# CHR_ver1.net
KiCad netlist of a schematic drawn in EAGLE
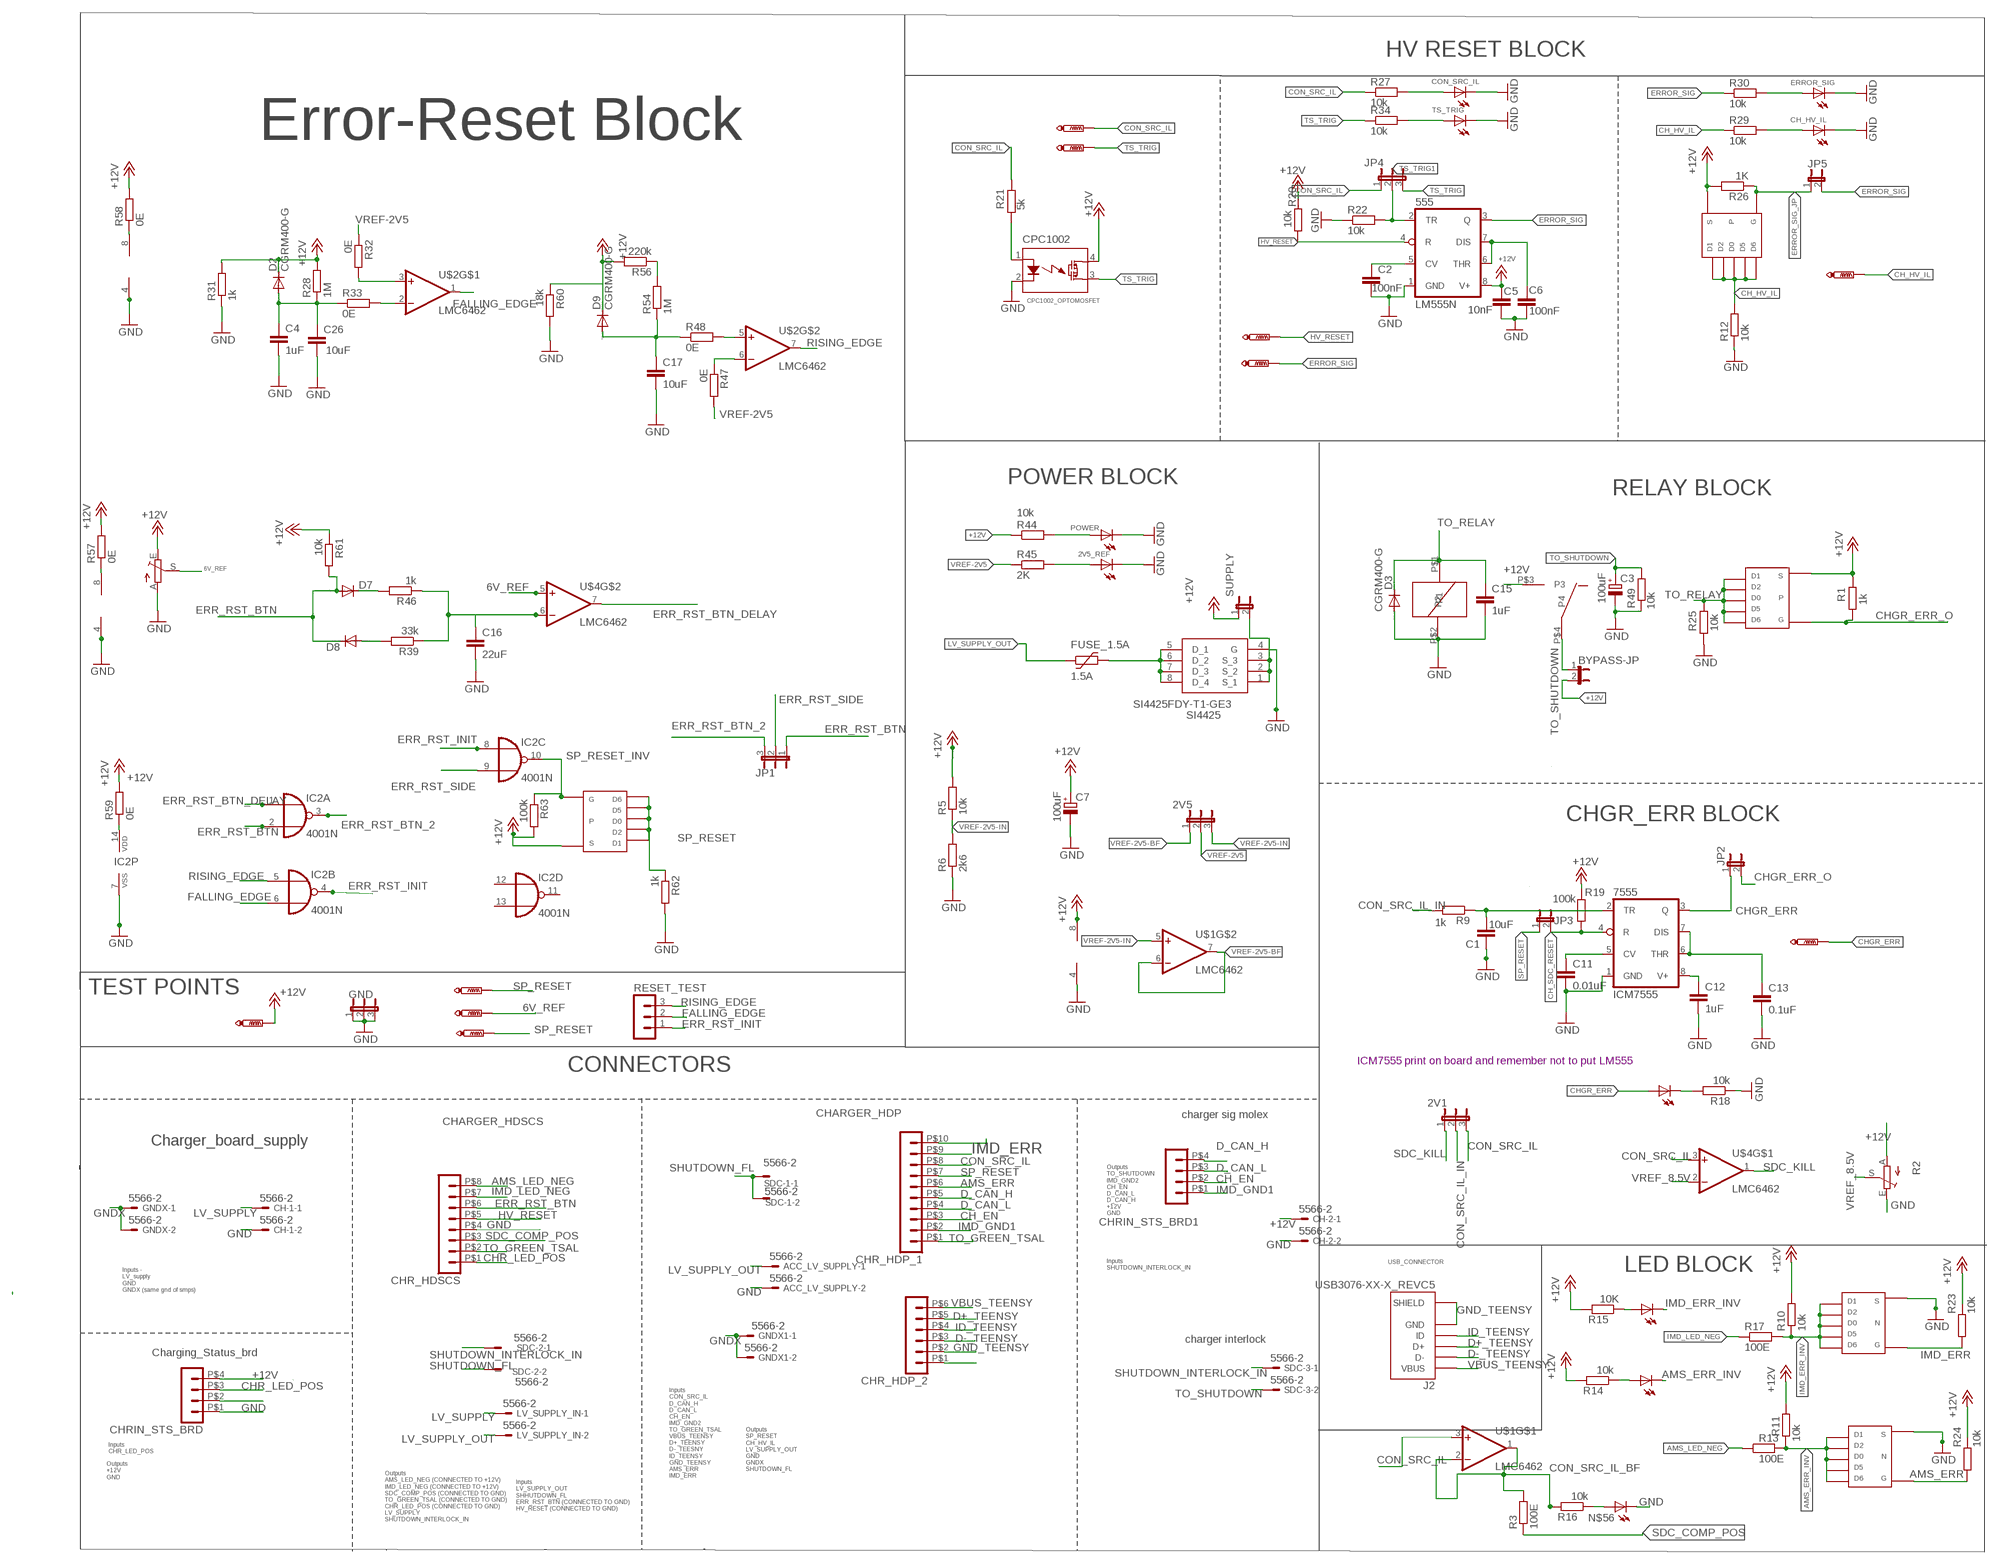
[diagram p0: schematic, sheet 1]

(export (version "E")
  (design (tool "Eeschema 10.0.6"))
  (components
    (comp (ref "+12V")
      (value "PTR1PAD1-13")
      (footprint "eagle-import:P1-13")
      (libsource (lib "eagle-import") (part "PTR1PAD1-13"))
    )
    (comp (ref "2V1")
      (value "JP2E")
      (footprint "eagle-import:JP2")
      (libsource (lib "eagle-import") (part "JP2E"))
    )
    (comp (ref "2V5")
      (value "JP2E")
      (footprint "eagle-import:JP2")
      (libsource (lib "eagle-import") (part "JP2E"))
    )
    (comp (ref "2V5_REF")
      (value "LED-FKIT-1206")
      (footprint "eagle-import:FKIT-LED-1206")
      (libsource (lib "eagle-import") (part "LED-FKIT-1206"))
    )
    (comp (ref "555")
      (value "LM555N")
      (footprint "eagle-import:DIL08")
      (libsource (lib "eagle-import") (part "555NLM"))
    )
    (comp (ref "7555")
      (value "ICM7555")
      (footprint "eagle-import:DIL08")
      (libsource (lib "eagle-import") (part "555NLM"))
    )
    (comp (ref "ACC_LV_SUPPLY")
      (value "5566-2")
      (footprint "eagle-import:5566-2")
      (fields (field (name "MF") "MOLEX"))
      (libsource (lib "eagle-import") (part "5566-2"))
    )
    (comp (ref "AMS")
      (value "LED-FKIT-1206")
      (footprint "eagle-import:FKIT-LED-1206")
      (libsource (lib "eagle-import") (part "LED-FKIT-1206"))
    )
    (comp (ref "AMS1")
      (value "LED-FKIT-1206")
      (footprint "eagle-import:FKIT-LED-1206")
      (libsource (lib "eagle-import") (part "LED-FKIT-1206"))
    )
    (comp (ref "BYPASS-JP")
      (value "JP1E")
      (footprint "eagle-import:JP1")
      (libsource (lib "eagle-import") (part "JP1E"))
    )
    (comp (ref "C1")
      (value "10uF")
      (footprint "eagle-import:C0805")
      (libsource (lib "eagle-import") (part "C-EUC0805"))
    )
    (comp (ref "C2")
      (value "100nF")
      (footprint "eagle-import:C0805")
      (libsource (lib "eagle-import") (part "C-EUC0805"))
    )
    (comp (ref "C3")
      (value "100uF")
      (footprint "eagle-import:E2,5-6")
      (libsource (lib "eagle-import") (part "CPOL-EUE2.5-6"))
    )
    (comp (ref "C4")
      (value "1uF")
      (footprint "eagle-import:C0805")
      (libsource (lib "eagle-import") (part "C-EUC0805"))
    )
    (comp (ref "C5")
      (value "10nF")
      (footprint "eagle-import:C0805")
      (libsource (lib "eagle-import") (part "C-EUC0805"))
    )
    (comp (ref "C6")
      (value "100nF")
      (footprint "eagle-import:C0805")
      (libsource (lib "eagle-import") (part "C-EUC0805"))
    )
    (comp (ref "C7")
      (value "100uF")
      (footprint "eagle-import:E2,5-6")
      (libsource (lib "eagle-import") (part "CPOL-EUE2.5-6"))
    )
    (comp (ref "C11")
      (value "0.01uF")
      (footprint "eagle-import:C0805")
      (libsource (lib "eagle-import") (part "C-EUC0805"))
    )
    (comp (ref "C12")
      (value "1uF")
      (footprint "eagle-import:C0805")
      (libsource (lib "eagle-import") (part "C-EUC0805"))
    )
    (comp (ref "C13")
      (value "0.1uF")
      (footprint "eagle-import:C0805")
      (libsource (lib "eagle-import") (part "C-EUC0805"))
    )
    (comp (ref "C15")
      (value "1uF")
      (footprint "eagle-import:C0805")
      (libsource (lib "eagle-import") (part "C-EUC0805"))
    )
    (comp (ref "C16")
      (value "22uF")
      (footprint "eagle-import:C0805")
      (libsource (lib "eagle-import") (part "C-EUC0805"))
    )
    (comp (ref "C17")
      (value "10uF")
      (footprint "eagle-import:C0805")
      (libsource (lib "eagle-import") (part "C-EUC0805"))
    )
    (comp (ref "C26")
      (value "10uF")
      (footprint "eagle-import:C0805")
      (libsource (lib "eagle-import") (part "C-EUC0805"))
    )
    (comp (ref "CH-1")
      (value "5566-2")
      (footprint "eagle-import:5566-2")
      (fields (field (name "MF") "MOLEX"))
      (libsource (lib "eagle-import") (part "5566-2"))
    )
    (comp (ref "CH-2")
      (value "5566-2")
      (footprint "eagle-import:5566-2")
      (fields (field (name "MF") "MOLEX"))
      (libsource (lib "eagle-import") (part "5566-2"))
    )
    (comp (ref "CH-HV-IL")
      (value "PTR1PAD1-13")
      (footprint "eagle-import:P1-13")
      (libsource (lib "eagle-import") (part "PTR1PAD1-13"))
    )
    (comp (ref "CHGR-ERR")
      (value "PTR1PAD1-13")
      (footprint "eagle-import:P1-13")
      (libsource (lib "eagle-import") (part "PTR1PAD1-13"))
    )
    (comp (ref "CHGR_ERR")
      (value "LED-FKIT-1206")
      (footprint "eagle-import:FKIT-LED-1206")
      (libsource (lib "eagle-import") (part "LED-FKIT-1206"))
    )
    (comp (ref "CHRIN_STS_BRD")
      (value "HEADER_POS4_44914-0401")
      (footprint "eagle-import:44914-0401")
      (libsource (lib "eagle-import") (part "HEADER_POS4_?44914-0401"))
    )
    (comp (ref "CHRIN_STS_BRD1")
      (value "HEADER_POS4_44914-0401")
      (footprint "eagle-import:44914-0401")
      (libsource (lib "eagle-import") (part "HEADER_POS4_?44914-0401"))
    )
    (comp (ref "CHR_HDP_1")
      (value "HEADER_POS10_44914-1001")
      (footprint "eagle-import:44914-1001")
      (libsource (lib "eagle-import") (part "HEADER_POS10_?44914-1001"))
    )
    (comp (ref "CHR_HDP_2")
      (value "HEADER_POS6_44914-0601")
      (footprint "eagle-import:44914-0601")
      (libsource (lib "eagle-import") (part "HEADER_POS6_?44914-0601"))
    )
    (comp (ref "CHR_HDSCS")
      (value "HEADER_POS8_44914-0801")
      (footprint "eagle-import:44914-0801")
      (libsource (lib "eagle-import") (part "HEADER_POS8_?44914-0801"))
    )
    (comp (ref "CH_HV_IL")
      (value "LED-FKIT-1206")
      (footprint "eagle-import:FKIT-LED-1206")
      (libsource (lib "eagle-import") (part "LED-FKIT-1206"))
    )
    (comp (ref "CON-SRC-IL")
      (value "PTR1PAD1-13")
      (footprint "eagle-import:P1-13")
      (libsource (lib "eagle-import") (part "PTR1PAD1-13"))
    )
    (comp (ref "CON_SRC_IL")
      (value "LED-FKIT-1206")
      (footprint "eagle-import:FKIT-LED-1206")
      (libsource (lib "eagle-import") (part "LED-FKIT-1206"))
    )
    (comp (ref "CPC1002")
      (value "CPC1002_OPTOMOSFET")
      (footprint "eagle-import:SOP04")
      (libsource (lib "eagle-import") (part "CPC1002_OPTOMOSFET"))
    )
    (comp (ref "D2")
      (value "CGRM400-G")
      (footprint "eagle-import:SOD-123_MINI-SMA")
      (libsource (lib "eagle-import") (part "CGRM400-G"))
    )
    (comp (ref "D3")
      (value "CGRM400-G")
      (footprint "eagle-import:SOD-123_MINI-SMA")
      (libsource (lib "eagle-import") (part "CGRM400-G"))
    )
    (comp (ref "D7")
      (value "DIODE-DO214AC")
      (footprint "eagle-import:DO214AC")
      (libsource (lib "eagle-import") (part "DIODE-DO214AC"))
    )
    (comp (ref "D8")
      (value "DIODE-DO214AC")
      (footprint "eagle-import:DO214AC")
      (libsource (lib "eagle-import") (part "DIODE-DO214AC"))
    )
    (comp (ref "D9")
      (value "CGRM400-G")
      (footprint "eagle-import:SOD-123_MINI-SMA")
      (libsource (lib "eagle-import") (part "CGRM400-G"))
    )
    (comp (ref "ERROR-SIG")
      (value "PTR1PAD1-13")
      (footprint "eagle-import:P1-13")
      (libsource (lib "eagle-import") (part "PTR1PAD1-13"))
    )
    (comp (ref "ERROR_SIG")
      (value "LED-FKIT-1206")
      (footprint "eagle-import:FKIT-LED-1206")
      (libsource (lib "eagle-import") (part "LED-FKIT-1206"))
    )
    (comp (ref "FUSE_1.5A")
      (value "1.5A")
      (footprint "eagle-import:1206L")
      (fields (field (name "MFR") "Littelfuse"))
      (libsource (lib "eagle-import") (part "1206L"))
    )
    (comp (ref "GND")
      (value "JP2E")
      (footprint "eagle-import:JP2")
      (libsource (lib "eagle-import") (part "JP2E"))
    )
    (comp (ref "GNDX")
      (value "5566-2")
      (footprint "eagle-import:5566-2")
      (fields (field (name "MF") "MOLEX"))
      (libsource (lib "eagle-import") (part "5566-2"))
    )
    (comp (ref "GNDX1")
      (value "5566-2")
      (footprint "eagle-import:5566-2")
      (fields (field (name "MF") "MOLEX"))
      (libsource (lib "eagle-import") (part "5566-2"))
    )
    (comp (ref "HV-RESET")
      (value "PTR1PAD1-13")
      (footprint "eagle-import:P1-13")
      (libsource (lib "eagle-import") (part "PTR1PAD1-13"))
    )
    (comp (ref "IC2")
      (value "4001N")
      (footprint "eagle-import:DIL14")
      (libsource (lib "eagle-import") (part "4001N"))
    )
    (comp (ref "IMD")
      (value "LED-FKIT-1206")
      (footprint "eagle-import:FKIT-LED-1206")
      (libsource (lib "eagle-import") (part "LED-FKIT-1206"))
    )
    (comp (ref "J2")
      (value "USB3076-XX-X_REVC5")
      (footprint "eagle-import:GCT_USB3076-XX-X_REVC5")
      (fields (field (name "MF") "Global Connector Technology") (field (name "MP") "USB3076-30-A"))
      (libsource (lib "eagle-import") (part "USB3076-XX-X_REVC5"))
    )
    (comp (ref "JP1")
      (value "JP2E")
      (footprint "eagle-import:JP2")
      (libsource (lib "eagle-import") (part "JP2E"))
    )
    (comp (ref "JP2")
      (value "JP1E")
      (footprint "eagle-import:JP1")
      (libsource (lib "eagle-import") (part "JP1E"))
    )
    (comp (ref "JP3")
      (value "JP1E")
      (footprint "eagle-import:JP1")
      (libsource (lib "eagle-import") (part "JP1E"))
    )
    (comp (ref "JP4")
      (value "JP2E")
      (footprint "eagle-import:JP2")
      (libsource (lib "eagle-import") (part "JP2E"))
    )
    (comp (ref "JP5")
      (value "JP1E")
      (footprint "eagle-import:JP1")
      (libsource (lib "eagle-import") (part "JP1E"))
    )
    (comp (ref "LV_SUPPLY_IN")
      (value "5566-2")
      (footprint "eagle-import:5566-2")
      (fields (field (name "MF") "MOLEX"))
      (libsource (lib "eagle-import") (part "5566-2"))
    )
    (comp (ref "POWER")
      (value "LED-FKIT-1206")
      (footprint "eagle-import:FKIT-LED-1206")
      (libsource (lib "eagle-import") (part "LED-FKIT-1206"))
    )
    (comp (ref "R1")
      (value "1k")
      (footprint "eagle-import:R0805")
      (libsource (lib "eagle-import") (part "R-EU_R0805"))
    )
    (comp (ref "R2")
      (value "TRIM_EU-S63S")
      (footprint "eagle-import:S63S")
      (libsource (lib "eagle-import") (part "TRIM_EU-S63S"))
    )
    (comp (ref "R3")
      (value "100E")
      (footprint "eagle-import:M0805")
      (libsource (lib "eagle-import") (part "rcl_334_R-EU_M0805"))
    )
    (comp (ref "R5")
      (value "10k")
      (footprint "eagle-import:R0805")
      (libsource (lib "eagle-import") (part "R-EU_R0805"))
    )
    (comp (ref "R6")
      (value "2k6")
      (footprint "eagle-import:R0805")
      (libsource (lib "eagle-import") (part "R-EU_R0805"))
    )
    (comp (ref "R9")
      (value "1k")
      (footprint "eagle-import:R0805")
      (libsource (lib "eagle-import") (part "R-EU_R0805"))
    )
    (comp (ref "R10")
      (value "10k")
      (footprint "eagle-import:R0805")
      (libsource (lib "eagle-import") (part "R-EU_R0805"))
    )
    (comp (ref "R11")
      (value "10k")
      (footprint "eagle-import:R0805")
      (libsource (lib "eagle-import") (part "R-EU_R0805"))
    )
    (comp (ref "R12")
      (value "10k")
      (footprint "eagle-import:R0805")
      (libsource (lib "eagle-import") (part "R-EU_R0805"))
    )
    (comp (ref "R13")
      (value "100E")
      (footprint "eagle-import:M0805")
      (libsource (lib "eagle-import") (part "rcl_334_R-EU_M0805"))
    )
    (comp (ref "R14")
      (value "10k")
      (footprint "eagle-import:M0805")
      (libsource (lib "eagle-import") (part "rcl_334_R-EU_M0805"))
    )
    (comp (ref "R15")
      (value "10K")
      (footprint "eagle-import:M0805")
      (libsource (lib "eagle-import") (part "rcl_334_R-EU_M0805"))
    )
    (comp (ref "R16")
      (value "10k")
      (footprint "eagle-import:M0805")
      (libsource (lib "eagle-import") (part "rcl_334_R-EU_M0805"))
    )
    (comp (ref "R17")
      (value "100E")
      (footprint "eagle-import:M0805")
      (libsource (lib "eagle-import") (part "rcl_334_R-EU_M0805"))
    )
    (comp (ref "R18")
      (value "10k")
      (footprint "eagle-import:R0805")
      (libsource (lib "eagle-import") (part "R-EU_R0805"))
    )
    (comp (ref "R19")
      (value "100k")
      (footprint "eagle-import:R0805")
      (libsource (lib "eagle-import") (part "R-EU_R0805"))
    )
    (comp (ref "R20")
      (value "10k")
      (footprint "eagle-import:R0805")
      (libsource (lib "eagle-import") (part "R-EU_R0805"))
    )
    (comp (ref "R21")
      (value "5k")
      (footprint "eagle-import:R0805")
      (libsource (lib "eagle-import") (part "R-EU_R0805"))
    )
    (comp (ref "R22")
      (value "10k")
      (footprint "eagle-import:R0805")
      (libsource (lib "eagle-import") (part "R-EU_R0805"))
    )
    (comp (ref "R23")
      (value "10k")
      (footprint "eagle-import:R0805")
      (libsource (lib "eagle-import") (part "R-EU_R0805"))
    )
    (comp (ref "R24")
      (value "10k")
      (footprint "eagle-import:R0805")
      (libsource (lib "eagle-import") (part "R-EU_R0805"))
    )
    (comp (ref "R25")
      (value "10k")
      (footprint "eagle-import:R0805")
      (libsource (lib "eagle-import") (part "R-EU_R0805"))
    )
    (comp (ref "R26")
      (value "1K")
      (footprint "eagle-import:R0805")
      (libsource (lib "eagle-import") (part "R-EU_R0805"))
    )
    (comp (ref "R27")
      (value "10k")
      (footprint "eagle-import:R0805")
      (libsource (lib "eagle-import") (part "R-EU_R0805"))
    )
    (comp (ref "R28")
      (value "1M")
      (footprint "eagle-import:R0805")
      (libsource (lib "eagle-import") (part "R-EU_R0805"))
    )
    (comp (ref "R29")
      (value "10k")
      (footprint "eagle-import:R0805")
      (libsource (lib "eagle-import") (part "R-EU_R0805"))
    )
    (comp (ref "R30")
      (value "10k")
      (footprint "eagle-import:R0805")
      (libsource (lib "eagle-import") (part "R-EU_R0805"))
    )
    (comp (ref "R31")
      (value "1k")
      (footprint "eagle-import:R0805")
      (libsource (lib "eagle-import") (part "R-EU_R0805"))
    )
    (comp (ref "R32")
      (value "0E")
      (footprint "eagle-import:R0805")
      (libsource (lib "eagle-import") (part "R-EU_R0805"))
    )
    (comp (ref "R33")
      (value "0E")
      (footprint "eagle-import:R0805")
      (libsource (lib "eagle-import") (part "R-EU_R0805"))
    )
    (comp (ref "R34")
      (value "10k")
      (footprint "eagle-import:R0805")
      (libsource (lib "eagle-import") (part "R-EU_R0805"))
    )
    (comp (ref "R39")
      (value "33k")
      (footprint "eagle-import:R0805")
      (libsource (lib "eagle-import") (part "R-EU_R0805"))
    )
    (comp (ref "R44")
      (value "10k")
      (footprint "eagle-import:R0805")
      (libsource (lib "eagle-import") (part "R-EU_R0805"))
    )
    (comp (ref "R45")
      (value "2K")
      (footprint "eagle-import:R0805")
      (libsource (lib "eagle-import") (part "R-EU_R0805"))
    )
    (comp (ref "R46")
      (value "1k")
      (footprint "eagle-import:R0805")
      (libsource (lib "eagle-import") (part "R-EU_R0805"))
    )
    (comp (ref "R47")
      (value "0E")
      (footprint "eagle-import:R0805")
      (libsource (lib "eagle-import") (part "R-EU_R0805"))
    )
    (comp (ref "R48")
      (value "0E")
      (footprint "eagle-import:R0805")
      (libsource (lib "eagle-import") (part "R-EU_R0805"))
    )
    (comp (ref "R49")
      (value "10k")
      (footprint "eagle-import:R0805")
      (libsource (lib "eagle-import") (part "R-EU_R0805"))
    )
    (comp (ref "R54")
      (value "1M")
      (footprint "eagle-import:R0805")
      (libsource (lib "eagle-import") (part "R-EU_R0805"))
    )
    (comp (ref "R56")
      (value "220k")
      (footprint "eagle-import:R0805")
      (libsource (lib "eagle-import") (part "R-EU_R0805"))
    )
    (comp (ref "R57")
      (value "0E")
      (footprint "eagle-import:R0805")
      (libsource (lib "eagle-import") (part "R-EU_R0805"))
    )
    (comp (ref "R58")
      (value "0E")
      (footprint "eagle-import:R0805")
      (libsource (lib "eagle-import") (part "R-EU_R0805"))
    )
    (comp (ref "R59")
      (value "0E")
      (footprint "eagle-import:R0805")
      (libsource (lib "eagle-import") (part "R-EU_R0805"))
    )
    (comp (ref "R60")
      (value "18k")
      (footprint "eagle-import:R0805")
      (libsource (lib "eagle-import") (part "R-EU_R0805"))
    )
    (comp (ref "R61")
      (value "10k")
      (footprint "eagle-import:R0805")
      (libsource (lib "eagle-import") (part "R-EU_R0805"))
    )
    (comp (ref "R62")
      (value "1k")
      (footprint "eagle-import:R0805")
      (libsource (lib "eagle-import") (part "R-EU_R0805"))
    )
    (comp (ref "R63")
      (value "100k")
      (footprint "eagle-import:R0805")
      (libsource (lib "eagle-import") (part "R-EU_R0805"))
    )
    (comp (ref "REF_POT1")
      (value "10k")
      (footprint "eagle-import:S63S")
      (libsource (lib "eagle-import") (part "TRIM_EU-S63S"))
    )
    (comp (ref "RESET_TEST")
      (value "MA03-1")
      (footprint "eagle-import:MA03-1")
      (libsource (lib "eagle-import") (part "MA03-1"))
    )
    (comp (ref "SDC-1")
      (value "5566-2")
      (footprint "eagle-import:5566-2")
      (fields (field (name "MF") "MOLEX"))
      (libsource (lib "eagle-import") (part "5566-2"))
    )
    (comp (ref "SDC-2")
      (value "5566-2")
      (footprint "eagle-import:5566-2")
      (fields (field (name "MF") "MOLEX"))
      (libsource (lib "eagle-import") (part "5566-2"))
    )
    (comp (ref "SDC-3")
      (value "5566-2")
      (footprint "eagle-import:5566-2")
      (fields (field (name "MF") "MOLEX"))
      (libsource (lib "eagle-import") (part "5566-2"))
    )
    (comp (ref "SI4425")
      (value "SI4425FDY-T1-GE3")
      (footprint "eagle-import:SOIC127P600X175-8N")
      (fields (field (name "MOUSER_PART_NUMBER") "78-SI4425FDY-T1-GE3"))
      (libsource (lib "eagle-import") (part "SI4425FDY-T1-GE3"))
    )
    (comp (ref "SP_RESET")
      (value "PTR1PAD1-13")
      (footprint "eagle-import:P1-13")
      (libsource (lib "eagle-import") (part "PTR1PAD1-13"))
    )
    (comp (ref "SP_RESET1")
      (value "PTR1PAD1-13")
      (footprint "eagle-import:P1-13")
      (libsource (lib "eagle-import") (part "PTR1PAD1-13"))
    )
    (comp (ref "SP_RESET2")
      (value "PTR1PAD1-13")
      (footprint "eagle-import:P1-13")
      (libsource (lib "eagle-import") (part "PTR1PAD1-13"))
    )
    (comp (ref "SUPPLY")
      (value "JP1E")
      (footprint "eagle-import:JP1")
      (libsource (lib "eagle-import") (part "JP1E"))
    )
    (comp (ref "TS-TRIG")
      (value "PTR1PAD1-13")
      (footprint "eagle-import:P1-13")
      (libsource (lib "eagle-import") (part "PTR1PAD1-13"))
    )
    (comp (ref "TS_TRIG")
      (value "LED-FKIT-1206")
      (footprint "eagle-import:FKIT-LED-1206")
      (libsource (lib "eagle-import") (part "LED-FKIT-1206"))
    )
    (comp (ref "U$1")
      (value "LMC6462")
      (footprint "eagle-import:S08")
      (libsource (lib "eagle-import") (part "LMC6462"))
    )
    (comp (ref "U$2")
      (value "LMC6462")
      (footprint "eagle-import:S08")
      (libsource (lib "eagle-import") (part "LMC6462"))
    )
    (comp (ref "U$3")
      (value "TSOP-6_PMOS")
      (footprint "eagle-import:TSOP-6_PMOS")
      (libsource (lib "eagle-import") (part "TSOP-6_MOS_TSOP-6_PMOS"))
    )
    (comp (ref "U$4")
      (value "LMC6462")
      (footprint "eagle-import:S08")
      (libsource (lib "eagle-import") (part "LMC6462"))
    )
    (comp (ref "U$5")
      (value "TSOP-6_NMOS")
      (footprint "eagle-import:TSOP-6_NMOS")
      (libsource (lib "eagle-import") (part "TSOP-6_NMOS"))
    )
    (comp (ref "U$7")
      (value "TSOP-6_NMOS")
      (footprint "eagle-import:TSOP-6_NMOS")
      (libsource (lib "eagle-import") (part "TSOP-6_NMOS"))
    )
    (comp (ref "U$8")
      (value "TSOP-6_PMOS")
      (footprint "eagle-import:TSOP-6_PMOS")
      (libsource (lib "eagle-import") (part "TSOP-6_PMOS"))
    )
    (comp (ref "U$9")
      (value "G6DN_RELAY")
      (footprint "eagle-import:G6DN_RELAY")
      (libsource (lib "eagle-import") (part "G6DN_RELAY"))
    )
    (comp (ref "U$11")
      (value "TSOP-6_PMOS")
      (footprint "eagle-import:TSOP-6_PMOS")
      (libsource (lib "eagle-import") (part "TSOP-6_MOS_TSOP-6_PMOS"))
    )
  )
  (nets
    (net (code "1") (name "+12V") (class "Default")
      (node (ref "+12V") (pin "TP") (pinfunction "TP_TP") (pintype "input"))
      (node (ref "555") (pin "8") (pinfunction "V+_8") (pintype "power_in"))
      (node (ref "7555") (pin "8") (pinfunction "V+_8") (pintype "power_in"))
      (node (ref "BYPASS-JP") (pin "2") (pinfunction "2_2") (pintype "passive"))
      (node (ref "C12") (pin "1") (pinfunction "1_1") (pintype "passive"))
      (node (ref "C5") (pin "1") (pinfunction "1_1") (pintype "passive"))
      (node (ref "C7") (pin "+") (pinfunction "+_+") (pintype "passive"))
      (node (ref "CH-2") (pin "1") (pinfunction "S_1") (pintype "passive"))
      (node (ref "CHRIN_STS_BRD") (pin "P$4") (pinfunction "4_P$4") (pintype "passive"))
      (node (ref "CPC1002") (pin "4") (pinfunction "4_4") (pintype "passive"))
      (node (ref "D2") (pin "C") (pinfunction "C_C") (pintype "passive"))
      (node (ref "D9") (pin "C") (pinfunction "C_C") (pintype "passive"))
      (node (ref "R1") (pin "2") (pinfunction "2_2") (pintype "passive"))
      (node (ref "R10") (pin "2") (pinfunction "2_2") (pintype "passive"))
      (node (ref "R11") (pin "2") (pinfunction "2_2") (pintype "passive"))
      (node (ref "R14") (pin "2") (pinfunction "2_2") (pintype "passive"))
      (node (ref "R15") (pin "2") (pinfunction "2_2") (pintype "passive"))
      (node (ref "R19") (pin "1") (pinfunction "1_1") (pintype "passive"))
      (node (ref "R2") (pin "A") (pinfunction "A_A") (pintype "passive"))
      (node (ref "R20") (pin "2") (pinfunction "2_2") (pintype "passive"))
      (node (ref "R23") (pin "2") (pinfunction "2_2") (pintype "passive"))
      (node (ref "R24") (pin "2") (pinfunction "2_2") (pintype "passive"))
      (node (ref "R26") (pin "2") (pinfunction "2_2") (pintype "passive"))
      (node (ref "R28") (pin "2") (pinfunction "2_2") (pintype "passive"))
      (node (ref "R31") (pin "2") (pinfunction "2_2") (pintype "passive"))
      (node (ref "R44") (pin "1") (pinfunction "1_1") (pintype "passive"))
      (node (ref "R5") (pin "2") (pinfunction "2_2") (pintype "passive"))
      (node (ref "R56") (pin "2") (pinfunction "2_2") (pintype "passive"))
      (node (ref "R57") (pin "2") (pinfunction "2_2") (pintype "passive"))
      (node (ref "R58") (pin "2") (pinfunction "2_2") (pintype "passive"))
      (node (ref "R59") (pin "2") (pinfunction "2_2") (pintype "passive"))
      (node (ref "R60") (pin "1") (pinfunction "1_1") (pintype "passive"))
      (node (ref "R61") (pin "1") (pinfunction "1_1") (pintype "passive"))
      (node (ref "R63") (pin "2") (pinfunction "2_2") (pintype "passive"))
      (node (ref "REF_POT1") (pin "E") (pinfunction "E_E") (pintype "passive"))
      (node (ref "SUPPLY") (pin "1") (pinfunction "1_1") (pintype "passive"))
      (node (ref "U$1") (pin "8") (pinfunction "V+_8") (pintype "power_in"))
      (node (ref "U$11") (pin "S") (pinfunction "S_S") (pintype "bidirectional"))
      (node (ref "U$3") (pin "S") (pinfunction "S_S") (pintype "bidirectional"))
      (node (ref "U$8") (pin "S") (pinfunction "S_S") (pintype "bidirectional"))
      (node (ref "U$9") (pin "P$3") (pinfunction "P3_P$3") (pintype "bidirectional"))
    )
    (net (code "2") (name "6V_REF") (class "Default")
      (node (ref "REF_POT1") (pin "S") (pinfunction "S_S") (pintype "passive"))
      (node (ref "SP_RESET1") (pin "TP") (pinfunction "TP_TP") (pintype "input"))
      (node (ref "U$4") (pin "5") (pinfunction "+IN_5") (pintype "input"))
    )
    (net (code "3") (name "AMS_ERR") (class "Default")
      (node (ref "CHR_HDP_1") (pin "P$6") (pinfunction "6_P$6") (pintype "passive"))
      (node (ref "R24") (pin "1") (pinfunction "1_1") (pintype "passive"))
      (node (ref "U$5") (pin "G") (pinfunction "G_G") (pintype "bidirectional"))
    )
    (net (code "4") (name "AMS_ERR_INV") (class "Default")
      (node (ref "AMS") (pin "C") (pinfunction "C_C") (pintype "passive"))
      (node (ref "R11") (pin "1") (pinfunction "1_1") (pintype "passive"))
      (node (ref "R13") (pin "2") (pinfunction "2_2") (pintype "passive"))
      (node (ref "U$5") (pin "1") (pinfunction "1_1") (pintype "bidirectional"))
      (node (ref "U$5") (pin "2") (pinfunction "2_2") (pintype "bidirectional"))
      (node (ref "U$5") (pin "5") (pinfunction "5_5") (pintype "bidirectional"))
      (node (ref "U$5") (pin "6") (pinfunction "6_6") (pintype "bidirectional"))
      (node (ref "U$5") (pin "D") (pinfunction "D0_D") (pintype "bidirectional"))
    )
    (net (code "5") (name "AMS_LED_NEG") (class "Default")
      (node (ref "CHR_HDSCS") (pin "P$8") (pinfunction "8_P$8") (pintype "passive"))
      (node (ref "R13") (pin "1") (pinfunction "1_1") (pintype "passive"))
    )
    (net (code "6") (name "CHGR_ERR") (class "Default")
      (node (ref "7555") (pin "3") (pinfunction "Q_3") (pintype "output"))
      (node (ref "CHGR-ERR") (pin "TP") (pinfunction "TP_TP") (pintype "input"))
      (node (ref "CHGR_ERR") (pin "A") (pinfunction "A_A") (pintype "passive"))
      (node (ref "JP2") (pin "1") (pinfunction "1_1") (pintype "passive"))
    )
    (net (code "7") (name "CHGR_ERR_O") (class "Default")
      (node (ref "JP2") (pin "2") (pinfunction "2_2") (pintype "passive"))
      (node (ref "R1") (pin "1") (pinfunction "1_1") (pintype "passive"))
      (node (ref "U$3") (pin "G") (pinfunction "G_G") (pintype "bidirectional"))
    )
    (net (code "8") (name "CHR_LED_POS") (class "Default")
      (node (ref "CHRIN_STS_BRD") (pin "P$3") (pinfunction "3_P$3") (pintype "passive"))
      (node (ref "CHR_HDSCS") (pin "P$1") (pinfunction "1_P$1") (pintype "passive"))
    )
    (net (code "9") (name "CH_EN") (class "Default")
      (node (ref "CHRIN_STS_BRD1") (pin "P$2") (pinfunction "2_P$2") (pintype "passive"))
      (node (ref "CHR_HDP_1") (pin "P$3") (pinfunction "3_P$3") (pintype "passive"))
    )
    (net (code "10") (name "CH_HV_IL") (class "Default")
      (node (ref "CH-HV-IL") (pin "TP") (pinfunction "TP_TP") (pintype "input"))
      (node (ref "CHR_HDP_1") (pin "P$10") (pinfunction "10_P$10") (pintype "passive"))
      (node (ref "R12") (pin "2") (pinfunction "2_2") (pintype "passive"))
      (node (ref "R29") (pin "1") (pinfunction "1_1") (pintype "passive"))
      (node (ref "U$8") (pin "1") (pinfunction "1_1") (pintype "bidirectional"))
      (node (ref "U$8") (pin "2") (pinfunction "2_2") (pintype "bidirectional"))
      (node (ref "U$8") (pin "5") (pinfunction "5_5") (pintype "bidirectional"))
      (node (ref "U$8") (pin "6") (pinfunction "6_6") (pintype "bidirectional"))
      (node (ref "U$8") (pin "D") (pinfunction "D0_D") (pintype "bidirectional"))
    )
    (net (code "11") (name "CH_SDC_RESET") (class "Default")
      (node (ref "7555") (pin "4") (pinfunction "R_4") (pintype "input"))
      (node (ref "JP3") (pin "2") (pinfunction "2_2") (pintype "passive"))
      (node (ref "R19") (pin "2") (pinfunction "2_2") (pintype "passive"))
    )
    (net (code "12") (name "CON_SRC_IL") (class "Default")
      (node (ref "2V1") (pin "3") (pinfunction "3_3") (pintype "passive"))
      (node (ref "CHR_HDP_1") (pin "P$8") (pinfunction "8_P$8") (pintype "passive"))
      (node (ref "CON-SRC-IL") (pin "TP") (pinfunction "TP_TP") (pintype "input"))
      (node (ref "JP4") (pin "1") (pinfunction "1_1") (pintype "passive"))
      (node (ref "R21") (pin "2") (pinfunction "2_2") (pintype "passive"))
      (node (ref "R27") (pin "1") (pinfunction "1_1") (pintype "passive"))
      (node (ref "U$1") (pin "3") (pinfunction "+IN_3") (pintype "input"))
      (node (ref "U$4") (pin "3") (pinfunction "+IN_3") (pintype "input"))
    )
    (net (code "13") (name "CON_SRC_IL_BF") (class "Default")
      (node (ref "R16") (pin "2") (pinfunction "2_2") (pintype "passive"))
      (node (ref "R3") (pin "2") (pinfunction "2_2") (pintype "passive"))
      (node (ref "U$1") (pin "1") (pinfunction "OUT_1") (pintype "output"))
      (node (ref "U$1") (pin "2") (pinfunction "-IN_2") (pintype "input"))
    )
    (net (code "14") (name "CON_SRC_IL_IN") (class "Default")
      (node (ref "2V1") (pin "2") (pinfunction "2_2") (pintype "passive"))
      (node (ref "R9") (pin "2") (pinfunction "2_2") (pintype "passive"))
    )
    (net (code "15") (name "D+_TEENSY") (class "Default")
      (node (ref "CHR_HDP_2") (pin "P$5") (pinfunction "5_P$5") (pintype "passive"))
      (node (ref "J2") (pin "3") (pinfunction "D+_3") (pintype "bidirectional"))
    )
    (net (code "16") (name "D-_TEENSY") (class "Default")
      (node (ref "CHR_HDP_2") (pin "P$3") (pinfunction "3_P$3") (pintype "passive"))
      (node (ref "J2") (pin "2") (pinfunction "D-_2") (pintype "bidirectional"))
    )
    (net (code "17") (name "D_CAN_H") (class "Default")
      (node (ref "CHRIN_STS_BRD1") (pin "P$4") (pinfunction "4_P$4") (pintype "passive"))
      (node (ref "CHR_HDP_1") (pin "P$5") (pinfunction "5_P$5") (pintype "passive"))
    )
    (net (code "18") (name "D_CAN_L") (class "Default")
      (node (ref "CHRIN_STS_BRD1") (pin "P$3") (pinfunction "3_P$3") (pintype "passive"))
      (node (ref "CHR_HDP_1") (pin "P$4") (pinfunction "4_P$4") (pintype "passive"))
    )
    (net (code "19") (name "ERROR_SIG") (class "Default")
      (node (ref "555") (pin "3") (pinfunction "Q_3") (pintype "output"))
      (node (ref "ERROR-SIG") (pin "TP") (pinfunction "TP_TP") (pintype "input"))
      (node (ref "JP5") (pin "2") (pinfunction "2_2") (pintype "passive"))
      (node (ref "R30") (pin "1") (pinfunction "1_1") (pintype "passive"))
    )
    (net (code "20") (name "ERROR_SIG_JP") (class "Default")
      (node (ref "JP5") (pin "1") (pinfunction "1_1") (pintype "passive"))
      (node (ref "R26") (pin "1") (pinfunction "1_1") (pintype "passive"))
      (node (ref "U$8") (pin "G") (pinfunction "G_G") (pintype "bidirectional"))
    )
    (net (code "21") (name "ERR_RST_BTN") (class "Default")
      (node (ref "CHR_HDSCS") (pin "P$6") (pinfunction "6_P$6") (pintype "passive"))
      (node (ref "D7") (pin "A") (pinfunction "A_A") (pintype "passive"))
      (node (ref "D8") (pin "C") (pinfunction "C_C") (pintype "passive"))
      (node (ref "IC2") (pin "2") (pinfunction "I1_2") (pintype "input"))
      (node (ref "JP1") (pin "1") (pinfunction "1_1") (pintype "passive"))
      (node (ref "R61") (pin "2") (pinfunction "2_2") (pintype "passive"))
    )
    (net (code "22") (name "ERR_RST_BTN_2") (class "Default")
      (node (ref "IC2") (pin "3") (pinfunction "O_3") (pintype "output"))
      (node (ref "JP1") (pin "3") (pinfunction "3_3") (pintype "passive"))
    )
    (net (code "23") (name "ERR_RST_BTN_DELAY") (class "Default")
      (node (ref "IC2") (pin "1") (pinfunction "I0_1") (pintype "input"))
      (node (ref "U$4") (pin "7") (pinfunction "OUT_7") (pintype "output"))
    )
    (net (code "24") (name "ERR_RST_INIT") (class "Default")
      (node (ref "IC2") (pin "4") (pinfunction "O_4") (pintype "output"))
      (node (ref "IC2") (pin "8") (pinfunction "I0_8") (pintype "input"))
      (node (ref "RESET_TEST") (pin "1") (pinfunction "1_1") (pintype "passive"))
    )
    (net (code "25") (name "ERR_RST_SIDE") (class "Default")
      (node (ref "IC2") (pin "9") (pinfunction "I1_9") (pintype "input"))
      (node (ref "JP1") (pin "2") (pinfunction "2_2") (pintype "passive"))
    )
    (net (code "26") (name "FALLING_EDGE") (class "Default")
      (node (ref "IC2") (pin "6") (pinfunction "I1_6") (pintype "input"))
      (node (ref "RESET_TEST") (pin "2") (pinfunction "2_2") (pintype "passive"))
      (node (ref "U$2") (pin "1") (pinfunction "OUT_1") (pintype "output"))
    )
    (net (code "27") (name "GND") (class "Default")
      (node (ref "2V5_REF") (pin "C") (pinfunction "C_C") (pintype "passive"))
      (node (ref "555") (pin "1") (pinfunction "GND_1") (pintype "power_in"))
      (node (ref "7555") (pin "1") (pinfunction "GND_1") (pintype "power_in"))
      (node (ref "ACC_LV_SUPPLY") (pin "2") (pinfunction "S_2") (pintype "passive"))
      (node (ref "AMS1") (pin "C") (pinfunction "C_C") (pintype "passive"))
      (node (ref "C1") (pin "1") (pinfunction "1_1") (pintype "passive"))
      (node (ref "C11") (pin "2") (pinfunction "2_2") (pintype "passive"))
      (node (ref "C12") (pin "2") (pinfunction "2_2") (pintype "passive"))
      (node (ref "C13") (pin "2") (pinfunction "2_2") (pintype "passive"))
      (node (ref "C15") (pin "2") (pinfunction "2_2") (pintype "passive"))
      (node (ref "C16") (pin "2") (pinfunction "2_2") (pintype "passive"))
      (node (ref "C17") (pin "2") (pinfunction "2_2") (pintype "passive"))
      (node (ref "C2") (pin "2") (pinfunction "2_2") (pintype "passive"))
      (node (ref "C26") (pin "2") (pinfunction "2_2") (pintype "passive"))
      (node (ref "C3") (pin "-") (pinfunction "-_-") (pintype "passive"))
      (node (ref "C4") (pin "2") (pinfunction "2_2") (pintype "passive"))
      (node (ref "C5") (pin "2") (pinfunction "2_2") (pintype "passive"))
      (node (ref "C6") (pin "2") (pinfunction "2_2") (pintype "passive"))
      (node (ref "C7") (pin "-") (pinfunction "-_-") (pintype "passive"))
      (node (ref "CH-1") (pin "2") (pinfunction "S_2") (pintype "passive"))
      (node (ref "CH-2") (pin "2") (pinfunction "S_2") (pintype "passive"))
      (node (ref "CHRIN_STS_BRD") (pin "P$1") (pinfunction "1_P$1") (pintype "passive"))
      (node (ref "CHR_HDSCS") (pin "P$4") (pinfunction "4_P$4") (pintype "passive"))
      (node (ref "CH_HV_IL") (pin "C") (pinfunction "C_C") (pintype "passive"))
      (node (ref "CON_SRC_IL") (pin "C") (pinfunction "C_C") (pintype "passive"))
      (node (ref "CPC1002") (pin "2") (pinfunction "2_2") (pintype "passive"))
      (node (ref "D3") (pin "A") (pinfunction "A_A") (pintype "passive"))
      (node (ref "ERROR_SIG") (pin "C") (pinfunction "C_C") (pintype "passive"))
      (node (ref "GND") (pin "1") (pinfunction "1_1") (pintype "passive"))
      (node (ref "GND") (pin "2") (pinfunction "2_2") (pintype "passive"))
      (node (ref "GND") (pin "3") (pinfunction "3_3") (pintype "passive"))
      (node (ref "IC2") (pin "7") (pinfunction "VSS_7") (pintype "power_in"))
      (node (ref "POWER") (pin "C") (pinfunction "C_C") (pintype "passive"))
      (node (ref "R12") (pin "1") (pinfunction "1_1") (pintype "passive"))
      (node (ref "R18") (pin "1") (pinfunction "1_1") (pintype "passive"))
      (node (ref "R2") (pin "E") (pinfunction "E_E") (pintype "passive"))
      (node (ref "R22") (pin "1") (pinfunction "1_1") (pintype "passive"))
      (node (ref "R25") (pin "1") (pinfunction "1_1") (pintype "passive"))
      (node (ref "R31") (pin "1") (pinfunction "1_1") (pintype "passive"))
      (node (ref "R49") (pin "1") (pinfunction "1_1") (pintype "passive"))
      (node (ref "R6") (pin "1") (pinfunction "1_1") (pintype "passive"))
      (node (ref "R60") (pin "2") (pinfunction "2_2") (pintype "passive"))
      (node (ref "R62") (pin "2") (pinfunction "2_2") (pintype "passive"))
      (node (ref "REF_POT1") (pin "A") (pinfunction "A_A") (pintype "passive"))
      (node (ref "SI4425") (pin "4") (pinfunction "G_4") (pintype "bidirectional"))
      (node (ref "TS_TRIG") (pin "C") (pinfunction "C_C") (pintype "passive"))
      (node (ref "U$1") (pin "4") (pinfunction "V-_4") (pintype "power_in"))
      (node (ref "U$2") (pin "4") (pinfunction "V-_4") (pintype "power_in"))
      (node (ref "U$4") (pin "4") (pinfunction "V-_4") (pintype "power_in"))
      (node (ref "U$5") (pin "S") (pinfunction "S_S") (pintype "bidirectional"))
      (node (ref "U$7") (pin "S") (pinfunction "S_S") (pintype "bidirectional"))
      (node (ref "U$9") (pin "P$2") (pinfunction "P2_P$2") (pintype "bidirectional"))
    )
    (net (code "28") (name "GNDX") (class "Default")
      (node (ref "GNDX") (pin "1") (pinfunction "S_1") (pintype "passive"))
      (node (ref "GNDX") (pin "2") (pinfunction "S_2") (pintype "passive"))
      (node (ref "GNDX1") (pin "1") (pinfunction "S_1") (pintype "passive"))
      (node (ref "GNDX1") (pin "2") (pinfunction "S_2") (pintype "passive"))
    )
    (net (code "29") (name "GND_TEENSY") (class "Default")
      (node (ref "CHR_HDP_2") (pin "P$2") (pinfunction "2_P$2") (pintype "passive"))
      (node (ref "J2") (pin "10") (pinfunction "SHIELD_10") (pintype "power_in"))
      (node (ref "J2") (pin "11") (pinfunction "SHIELD_11") (pintype "power_in"))
      (node (ref "J2") (pin "5") (pinfunction "GND_5") (pintype "power_in"))
      (node (ref "J2") (pin "6") (pinfunction "SHIELD_6") (pintype "power_in"))
      (node (ref "J2") (pin "7") (pinfunction "SHIELD_7") (pintype "power_in"))
      (node (ref "J2") (pin "8") (pinfunction "SHIELD_8") (pintype "power_in"))
      (node (ref "J2") (pin "9") (pinfunction "SHIELD_9") (pintype "power_in"))
    )
    (net (code "30") (name "HV_RESET") (class "Default")
      (node (ref "555") (pin "4") (pinfunction "R_4") (pintype "input"))
      (node (ref "CHR_HDSCS") (pin "P$5") (pinfunction "5_P$5") (pintype "passive"))
      (node (ref "HV-RESET") (pin "TP") (pinfunction "TP_TP") (pintype "input"))
      (node (ref "R20") (pin "1") (pinfunction "1_1") (pintype "passive"))
    )
    (net (code "31") (name "ID_TEENSY") (class "Default")
      (node (ref "CHR_HDP_2") (pin "P$4") (pinfunction "4_P$4") (pintype "passive"))
      (node (ref "J2") (pin "4") (pinfunction "ID_4") (pintype "bidirectional"))
    )
    (net (code "32") (name "IMD_ERR") (class "Default")
      (node (ref "CHR_HDP_1") (pin "P$9") (pinfunction "9_P$9") (pintype "passive"))
      (node (ref "R23") (pin "1") (pinfunction "1_1") (pintype "passive"))
      (node (ref "U$7") (pin "G") (pinfunction "G_G") (pintype "bidirectional"))
    )
    (net (code "33") (name "IMD_ERR_INV") (class "Default")
      (node (ref "IMD") (pin "C") (pinfunction "C_C") (pintype "passive"))
      (node (ref "R10") (pin "1") (pinfunction "1_1") (pintype "passive"))
      (node (ref "R17") (pin "2") (pinfunction "2_2") (pintype "passive"))
      (node (ref "U$7") (pin "1") (pinfunction "1_1") (pintype "bidirectional"))
      (node (ref "U$7") (pin "2") (pinfunction "2_2") (pintype "bidirectional"))
      (node (ref "U$7") (pin "5") (pinfunction "5_5") (pintype "bidirectional"))
      (node (ref "U$7") (pin "6") (pinfunction "6_6") (pintype "bidirectional"))
      (node (ref "U$7") (pin "D") (pinfunction "D0_D") (pintype "bidirectional"))
    )
    (net (code "34") (name "IMD_GND1") (class "Default")
      (node (ref "CHRIN_STS_BRD1") (pin "P$1") (pinfunction "1_P$1") (pintype "passive"))
      (node (ref "CHR_HDP_1") (pin "P$2") (pinfunction "2_P$2") (pintype "passive"))
    )
    (net (code "35") (name "IMD_LED_NEG") (class "Default")
      (node (ref "CHR_HDSCS") (pin "P$7") (pinfunction "7_P$7") (pintype "passive"))
      (node (ref "R17") (pin "1") (pinfunction "1_1") (pintype "passive"))
    )
    (net (code "36") (name "LV_SUPPLY") (class "Default")
      (node (ref "CH-1") (pin "1") (pinfunction "S_1") (pintype "passive"))
      (node (ref "LV_SUPPLY_IN") (pin "1") (pinfunction "S_1") (pintype "passive"))
    )
    (net (code "37") (name "LV_SUPPLY_OUT") (class "Default")
      (node (ref "ACC_LV_SUPPLY") (pin "1") (pinfunction "S_1") (pintype "passive"))
      (node (ref "FUSE_1.5A") (pin "P$1") (pinfunction "1_P$1") (pintype "passive"))
      (node (ref "LV_SUPPLY_IN") (pin "2") (pinfunction "S_2") (pintype "passive"))
    )
    (net (code "38") (name "N$56") (class "Default")
      (node (ref "AMS1") (pin "A") (pinfunction "A_A") (pintype "passive"))
      (node (ref "R16") (pin "1") (pinfunction "1_1") (pintype "passive"))
    )
    (net (code "39") (name "Net-(2V5_REF-PadA)") (class "Default")
      (node (ref "2V5_REF") (pin "A") (pinfunction "A_A") (pintype "passive"))
      (node (ref "R45") (pin "2") (pinfunction "2_2") (pintype "passive"))
    )
    (net (code "40") (name "Net-(555-CV)") (class "Default")
      (node (ref "555") (pin "5") (pinfunction "CV_5") (pintype "input"))
      (node (ref "C2") (pin "1") (pinfunction "1_1") (pintype "passive"))
    )
    (net (code "41") (name "Net-(555-DIS)") (class "Default")
      (node (ref "555") (pin "6") (pinfunction "THR_6") (pintype "input"))
      (node (ref "555") (pin "7") (pinfunction "DIS_7") (pintype "input"))
      (node (ref "C6") (pin "1") (pinfunction "1_1") (pintype "passive"))
    )
    (net (code "42") (name "Net-(7555-CV)") (class "Default")
      (node (ref "7555") (pin "5") (pinfunction "CV_5") (pintype "input"))
      (node (ref "C11") (pin "1") (pinfunction "1_1") (pintype "passive"))
    )
    (net (code "43") (name "Net-(7555-DIS)") (class "Default")
      (node (ref "7555") (pin "6") (pinfunction "THR_6") (pintype "input"))
      (node (ref "7555") (pin "7") (pinfunction "DIS_7") (pintype "input"))
      (node (ref "C13") (pin "1") (pinfunction "1_1") (pintype "passive"))
    )
    (net (code "44") (name "Net-(7555-TR)") (class "Default")
      (node (ref "7555") (pin "2") (pinfunction "TR_2") (pintype "input"))
      (node (ref "C1") (pin "2") (pinfunction "2_2") (pintype "passive"))
      (node (ref "R9") (pin "1") (pinfunction "1_1") (pintype "passive"))
    )
    (net (code "45") (name "Net-(AMS-PadA)") (class "Default")
      (node (ref "AMS") (pin "A") (pinfunction "A_A") (pintype "passive"))
      (node (ref "R14") (pin "1") (pinfunction "1_1") (pintype "passive"))
    )
    (net (code "46") (name "Net-(C17-Pad1)") (class "Default")
      (node (ref "C17") (pin "1") (pinfunction "1_1") (pintype "passive"))
      (node (ref "D9") (pin "A") (pinfunction "A_A") (pintype "passive"))
      (node (ref "R48") (pin "1") (pinfunction "1_1") (pintype "passive"))
      (node (ref "R54") (pin "1") (pinfunction "1_1") (pintype "passive"))
    )
    (net (code "47") (name "Net-(C26-Pad1)") (class "Default")
      (node (ref "C26") (pin "1") (pinfunction "1_1") (pintype "passive"))
      (node (ref "C4") (pin "1") (pinfunction "1_1") (pintype "passive"))
      (node (ref "D2") (pin "A") (pinfunction "A_A") (pintype "passive"))
      (node (ref "R28") (pin "1") (pinfunction "1_1") (pintype "passive"))
      (node (ref "R33") (pin "1") (pinfunction "1_1") (pintype "passive"))
    )
    (net (code "48") (name "Net-(CHGR_ERR-PadC)") (class "Default")
      (node (ref "CHGR_ERR") (pin "C") (pinfunction "C_C") (pintype "passive"))
      (node (ref "R18") (pin "2") (pinfunction "2_2") (pintype "passive"))
    )
    (net (code "49") (name "Net-(CH_HV_IL-PadA)") (class "Default")
      (node (ref "CH_HV_IL") (pin "A") (pinfunction "A_A") (pintype "passive"))
      (node (ref "R29") (pin "2") (pinfunction "2_2") (pintype "passive"))
    )
    (net (code "50") (name "Net-(CON_SRC_IL-PadA)") (class "Default")
      (node (ref "CON_SRC_IL") (pin "A") (pinfunction "A_A") (pintype "passive"))
      (node (ref "R27") (pin "2") (pinfunction "2_2") (pintype "passive"))
    )
    (net (code "51") (name "Net-(CPC1002-Pad1)") (class "Default")
      (node (ref "CPC1002") (pin "1") (pinfunction "1_1") (pintype "passive"))
      (node (ref "R21") (pin "1") (pinfunction "1_1") (pintype "passive"))
    )
    (net (code "52") (name "Net-(D7-PadC)") (class "Default")
      (node (ref "D7") (pin "C") (pinfunction "C_C") (pintype "passive"))
      (node (ref "R46") (pin "2") (pinfunction "2_2") (pintype "passive"))
    )
    (net (code "53") (name "Net-(D8-PadA)") (class "Default")
      (node (ref "D8") (pin "A") (pinfunction "A_A") (pintype "passive"))
      (node (ref "R39") (pin "2") (pinfunction "2_2") (pintype "passive"))
    )
    (net (code "54") (name "Net-(ERROR_SIG-PadA)") (class "Default")
      (node (ref "ERROR_SIG") (pin "A") (pinfunction "A_A") (pintype "passive"))
      (node (ref "R30") (pin "2") (pinfunction "2_2") (pintype "passive"))
    )
    (net (code "55") (name "Net-(FUSE_1.5A-2)") (class "Default")
      (node (ref "FUSE_1.5A") (pin "P$2") (pinfunction "2_P$2") (pintype "passive"))
      (node (ref "SI4425") (pin "5") (pinfunction "D_1_5") (pintype "bidirectional"))
      (node (ref "SI4425") (pin "6") (pinfunction "D_2_6") (pintype "bidirectional"))
      (node (ref "SI4425") (pin "7") (pinfunction "D_3_7") (pintype "bidirectional"))
      (node (ref "SI4425") (pin "8") (pinfunction "D_4_8") (pintype "bidirectional"))
    )
    (net (code "56") (name "Net-(IC2E-VDD)") (class "Default")
      (node (ref "IC2") (pin "14") (pinfunction "VDD_14") (pintype "power_in"))
      (node (ref "R59") (pin "1") (pinfunction "1_1") (pintype "passive"))
    )
    (net (code "57") (name "Net-(IMD-PadA)") (class "Default")
      (node (ref "IMD") (pin "A") (pinfunction "A_A") (pintype "passive"))
      (node (ref "R15") (pin "1") (pinfunction "1_1") (pintype "passive"))
    )
    (net (code "58") (name "Net-(POWER-PadA)") (class "Default")
      (node (ref "POWER") (pin "A") (pinfunction "A_A") (pintype "passive"))
      (node (ref "R44") (pin "2") (pinfunction "2_2") (pintype "passive"))
    )
    (net (code "59") (name "Net-(R34-Pad2)") (class "Default")
      (node (ref "R34") (pin "2") (pinfunction "2_2") (pintype "passive"))
      (node (ref "TS_TRIG") (pin "A") (pinfunction "A_A") (pintype "passive"))
    )
    (net (code "60") (name "Net-(R54-Pad2)") (class "Default")
      (node (ref "R54") (pin "2") (pinfunction "2_2") (pintype "passive"))
      (node (ref "R56") (pin "1") (pinfunction "1_1") (pintype "passive"))
    )
    (net (code "61") (name "Net-(SI4425-S_1)") (class "Default")
      (node (ref "SI4425") (pin "1") (pinfunction "S_1_1") (pintype "bidirectional"))
      (node (ref "SI4425") (pin "2") (pinfunction "S_2_2") (pintype "bidirectional"))
      (node (ref "SI4425") (pin "3") (pinfunction "S_3_3") (pintype "bidirectional"))
      (node (ref "SUPPLY") (pin "2") (pinfunction "2_2") (pintype "passive"))
    )
    (net (code "62") (name "Net-(U$2A-+IN)") (class "Default")
      (node (ref "R32") (pin "2") (pinfunction "2_2") (pintype "passive"))
      (node (ref "U$2") (pin "3") (pinfunction "+IN_3") (pintype "input"))
    )
    (net (code "63") (name "Net-(U$2A--IN)") (class "Default")
      (node (ref "R33") (pin "2") (pinfunction "2_2") (pintype "passive"))
      (node (ref "U$2") (pin "2") (pinfunction "-IN_2") (pintype "input"))
    )
    (net (code "64") (name "Net-(U$2B-+IN)") (class "Default")
      (node (ref "R48") (pin "2") (pinfunction "2_2") (pintype "passive"))
      (node (ref "U$2") (pin "5") (pinfunction "+IN_5") (pintype "input"))
    )
    (net (code "65") (name "Net-(U$2B--IN)") (class "Default")
      (node (ref "R47") (pin "1") (pinfunction "1_1") (pintype "passive"))
      (node (ref "U$2") (pin "6") (pinfunction "-IN_6") (pintype "input"))
    )
    (net (code "66") (name "Net-(U$2C-V+)") (class "Default")
      (node (ref "R58") (pin "1") (pinfunction "1_1") (pintype "passive"))
      (node (ref "U$2") (pin "8") (pinfunction "V+_8") (pintype "power_in"))
    )
    (net (code "67") (name "Net-(U$4B--IN)") (class "Default")
      (node (ref "C16") (pin "1") (pinfunction "1_1") (pintype "passive"))
      (node (ref "R39") (pin "1") (pinfunction "1_1") (pintype "passive"))
      (node (ref "R46") (pin "1") (pinfunction "1_1") (pintype "passive"))
      (node (ref "U$4") (pin "6") (pinfunction "-IN_6") (pintype "input"))
    )
    (net (code "68") (name "Net-(U$4C-V+)") (class "Default")
      (node (ref "R57") (pin "1") (pinfunction "1_1") (pintype "passive"))
      (node (ref "U$4") (pin "8") (pinfunction "V+_8") (pintype "power_in"))
    )
    (net (code "69") (name "RISING_EDGE") (class "Default")
      (node (ref "IC2") (pin "5") (pinfunction "I0_5") (pintype "input"))
      (node (ref "RESET_TEST") (pin "3") (pinfunction "3_3") (pintype "passive"))
      (node (ref "U$2") (pin "7") (pinfunction "OUT_7") (pintype "output"))
    )
    (net (code "70") (name "SDC_COMP_POS") (class "Default")
      (node (ref "CHR_HDSCS") (pin "P$3") (pinfunction "3_P$3") (pintype "passive"))
      (node (ref "R3") (pin "1") (pinfunction "1_1") (pintype "passive"))
    )
    (net (code "71") (name "SDC_KILL") (class "Default")
      (node (ref "2V1") (pin "1") (pinfunction "1_1") (pintype "passive"))
      (node (ref "U$4") (pin "1") (pinfunction "OUT_1") (pintype "output"))
    )
    (net (code "72") (name "SHUTDOWN_FL") (class "Default")
      (node (ref "SDC-1") (pin "1") (pinfunction "S_1") (pintype "passive"))
      (node (ref "SDC-1") (pin "2") (pinfunction "S_2") (pintype "passive"))
      (node (ref "SDC-2") (pin "2") (pinfunction "S_2") (pintype "passive"))
    )
    (net (code "73") (name "SHUTDOWN_INTERLOCK_IN") (class "Default")
      (node (ref "SDC-2") (pin "1") (pinfunction "S_1") (pintype "passive"))
      (node (ref "SDC-3") (pin "1") (pinfunction "S_1") (pintype "passive"))
    )
    (net (code "74") (name "SP_RESET") (class "Default")
      (node (ref "CHR_HDP_1") (pin "P$7") (pinfunction "7_P$7") (pintype "passive"))
      (node (ref "JP3") (pin "1") (pinfunction "1_1") (pintype "passive"))
      (node (ref "R62") (pin "1") (pinfunction "1_1") (pintype "passive"))
      (node (ref "SP_RESET") (pin "TP") (pinfunction "TP_TP") (pintype "input"))
      (node (ref "SP_RESET2") (pin "TP") (pinfunction "TP_TP") (pintype "input"))
      (node (ref "U$11") (pin "1") (pinfunction "1_1") (pintype "bidirectional"))
      (node (ref "U$11") (pin "2") (pinfunction "2_2") (pintype "bidirectional"))
      (node (ref "U$11") (pin "5") (pinfunction "5_5") (pintype "bidirectional"))
      (node (ref "U$11") (pin "6") (pinfunction "6_6") (pintype "bidirectional"))
      (node (ref "U$11") (pin "D") (pinfunction "D0_D") (pintype "bidirectional"))
    )
    (net (code "75") (name "SP_RESET_INV") (class "Default")
      (node (ref "IC2") (pin "10") (pinfunction "O_10") (pintype "output"))
      (node (ref "R63") (pin "1") (pinfunction "1_1") (pintype "passive"))
      (node (ref "U$11") (pin "G") (pinfunction "G_G") (pintype "bidirectional"))
    )
    (net (code "76") (name "TO_GREEN_TSAL") (class "Default")
      (node (ref "CHR_HDP_1") (pin "P$1") (pinfunction "1_P$1") (pintype "passive"))
      (node (ref "CHR_HDSCS") (pin "P$2") (pinfunction "2_P$2") (pintype "passive"))
    )
    (net (code "77") (name "TO_RELAY") (class "Default")
      (node (ref "C15") (pin "1") (pinfunction "1_1") (pintype "passive"))
      (node (ref "D3") (pin "C") (pinfunction "C_C") (pintype "passive"))
      (node (ref "R25") (pin "2") (pinfunction "2_2") (pintype "passive"))
      (node (ref "U$3") (pin "1") (pinfunction "1_1") (pintype "bidirectional"))
      (node (ref "U$3") (pin "2") (pinfunction "2_2") (pintype "bidirectional"))
      (node (ref "U$3") (pin "5") (pinfunction "5_5") (pintype "bidirectional"))
      (node (ref "U$3") (pin "6") (pinfunction "6_6") (pintype "bidirectional"))
      (node (ref "U$3") (pin "D") (pinfunction "D0_D") (pintype "bidirectional"))
      (node (ref "U$9") (pin "P$1") (pinfunction "P1_P$1") (pintype "bidirectional"))
    )
    (net (code "78") (name "TO_SHUTDOWN") (class "Default")
      (node (ref "BYPASS-JP") (pin "1") (pinfunction "1_1") (pintype "passive"))
      (node (ref "C3") (pin "+") (pinfunction "+_+") (pintype "passive"))
      (node (ref "R49") (pin "2") (pinfunction "2_2") (pintype "passive"))
      (node (ref "SDC-3") (pin "2") (pinfunction "S_2") (pintype "passive"))
      (node (ref "U$9") (pin "P$4") (pinfunction "P4_P$4") (pintype "bidirectional"))
    )
    (net (code "79") (name "TS_TRIG") (class "Default")
      (node (ref "CPC1002") (pin "3") (pinfunction "3_3") (pintype "passive"))
      (node (ref "JP4") (pin "3") (pinfunction "3_3") (pintype "passive"))
      (node (ref "R34") (pin "1") (pinfunction "1_1") (pintype "passive"))
      (node (ref "TS-TRIG") (pin "TP") (pinfunction "TP_TP") (pintype "input"))
    )
    (net (code "80") (name "TS_TRIG1") (class "Default")
      (node (ref "555") (pin "2") (pinfunction "TR_2") (pintype "input"))
      (node (ref "JP4") (pin "2") (pinfunction "2_2") (pintype "passive"))
      (node (ref "R22") (pin "2") (pinfunction "2_2") (pintype "passive"))
    )
    (net (code "81") (name "VBUS_TEENSY") (class "Default")
      (node (ref "CHR_HDP_2") (pin "P$6") (pinfunction "6_P$6") (pintype "passive"))
      (node (ref "J2") (pin "1") (pinfunction "VBUS_1") (pintype "power_in"))
    )
    (net (code "82") (name "VREF-2V5") (class "Default")
      (node (ref "2V5") (pin "2") (pinfunction "2_2") (pintype "passive"))
      (node (ref "R32") (pin "1") (pinfunction "1_1") (pintype "passive"))
      (node (ref "R45") (pin "1") (pinfunction "1_1") (pintype "passive"))
      (node (ref "R47") (pin "2") (pinfunction "2_2") (pintype "passive"))
    )
    (net (code "83") (name "VREF-2V5-BF") (class "Default")
      (node (ref "2V5") (pin "1") (pinfunction "1_1") (pintype "passive"))
      (node (ref "U$1") (pin "6") (pinfunction "-IN_6") (pintype "input"))
      (node (ref "U$1") (pin "7") (pinfunction "OUT_7") (pintype "output"))
    )
    (net (code "84") (name "VREF-2V5-IN") (class "Default")
      (node (ref "2V5") (pin "3") (pinfunction "3_3") (pintype "passive"))
      (node (ref "R5") (pin "1") (pinfunction "1_1") (pintype "passive"))
      (node (ref "R6") (pin "2") (pinfunction "2_2") (pintype "passive"))
      (node (ref "U$1") (pin "5") (pinfunction "+IN_5") (pintype "input"))
    )
    (net (code "85") (name "VREF_8.5V") (class "Default")
      (node (ref "R2") (pin "S") (pinfunction "S_S") (pintype "passive"))
      (node (ref "U$4") (pin "2") (pinfunction "-IN_2") (pintype "input"))
    )
    (net (code "86") (name "unconnected-(CHRIN_STS_BRD-2-PadP$2)") (class "Default")
      (node (ref "CHRIN_STS_BRD") (pin "P$2") (pinfunction "2_P$2") (pintype "passive"))
    )
    (net (code "87") (name "unconnected-(CHR_HDP_2-1-PadP$1)") (class "Default")
      (node (ref "CHR_HDP_2") (pin "P$1") (pinfunction "1_P$1") (pintype "passive"))
    )
    (net (code "88") (name "unconnected-(IC2D-I0-Pad12)") (class "Default")
      (node (ref "IC2") (pin "12") (pinfunction "I0_12") (pintype "input"))
    )
    (net (code "89") (name "unconnected-(IC2D-I1-Pad13)") (class "Default")
      (node (ref "IC2") (pin "13") (pinfunction "I1_13") (pintype "input"))
    )
    (net (code "90") (name "unconnected-(IC2D-O-Pad11)") (class "Default")
      (node (ref "IC2") (pin "11") (pinfunction "O_11") (pintype "output"))
    )
  )
)
